# BMS_AFE_-_Cell_Inputs.net
KiCad netlist of a schematic drawn in Altium Designer
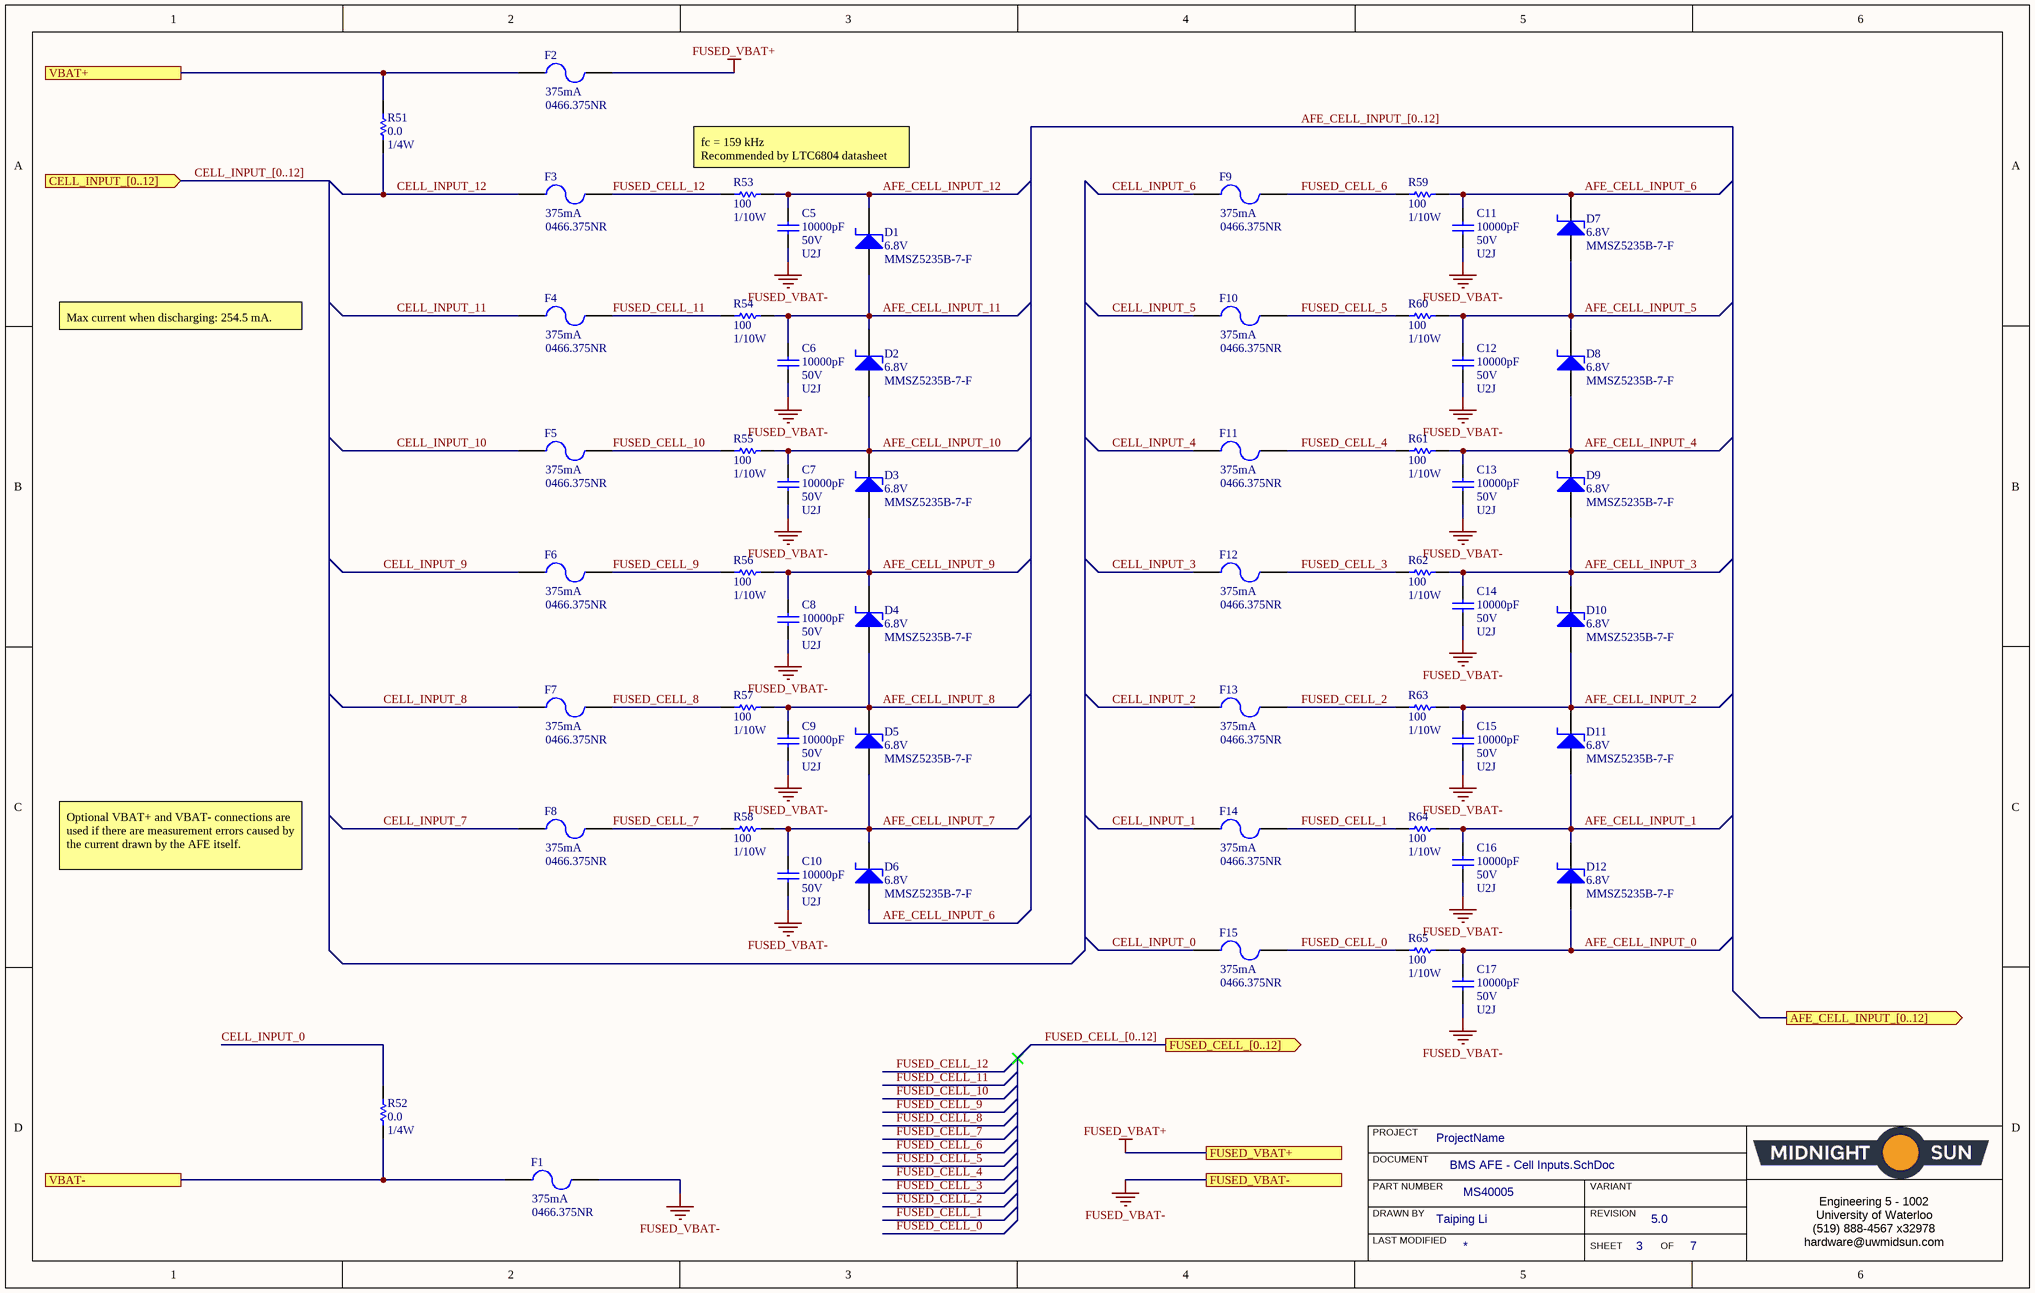
[diagram p0: BMS AFE - Cell Inputs.SchDoc]

(export (version "E")
  (design (tool "Eeschema 10.0.6"))
  (components
    (comp (ref "C5")
      (value "CAP CER 10nF 50V 5% X7R 0603")
      (footprint "CAP, 0603")
      (description "10000pF ±5% 50V Ceramic Capacitor U2J 0603 (1608 Metric)")
      (fields
        (field (name "TOLERANCE") "±5%")
        (field (name "CAPACITANCE") "10000pF")
        (field (name "VOLTAGE") "50V")
        (field (name "TEMPERATURE COEFFICIENT") "U2J")
      )
      (libsource (lib "Schematic Diagrams") (part "CAP CER 10nF 50V 5% X7R 0603"))
    )
    (comp (ref "C6")
      (value "CAP CER 10nF 50V 5% X7R 0603")
      (footprint "CAP, 0603")
      (description "10000pF ±5% 50V Ceramic Capacitor U2J 0603 (1608 Metric)")
      (fields
        (field (name "TOLERANCE") "±5%")
        (field (name "CAPACITANCE") "10000pF")
        (field (name "VOLTAGE") "50V")
        (field (name "TEMPERATURE COEFFICIENT") "U2J")
      )
      (libsource (lib "Schematic Diagrams") (part "CAP CER 10nF 50V 5% X7R 0603"))
    )
    (comp (ref "C7")
      (value "CAP CER 10nF 50V 5% X7R 0603")
      (footprint "CAP, 0603")
      (description "10000pF ±5% 50V Ceramic Capacitor U2J 0603 (1608 Metric)")
      (fields
        (field (name "TOLERANCE") "±5%")
        (field (name "CAPACITANCE") "10000pF")
        (field (name "VOLTAGE") "50V")
        (field (name "TEMPERATURE COEFFICIENT") "U2J")
      )
      (libsource (lib "Schematic Diagrams") (part "CAP CER 10nF 50V 5% X7R 0603"))
    )
    (comp (ref "C8")
      (value "CAP CER 10nF 50V 5% X7R 0603")
      (footprint "CAP, 0603")
      (description "10000pF ±5% 50V Ceramic Capacitor U2J 0603 (1608 Metric)")
      (fields
        (field (name "TOLERANCE") "±5%")
        (field (name "CAPACITANCE") "10000pF")
        (field (name "VOLTAGE") "50V")
        (field (name "TEMPERATURE COEFFICIENT") "U2J")
      )
      (libsource (lib "Schematic Diagrams") (part "CAP CER 10nF 50V 5% X7R 0603"))
    )
    (comp (ref "C9")
      (value "CAP CER 10nF 50V 5% X7R 0603")
      (footprint "CAP, 0603")
      (description "10000pF ±5% 50V Ceramic Capacitor U2J 0603 (1608 Metric)")
      (fields
        (field (name "TOLERANCE") "±5%")
        (field (name "CAPACITANCE") "10000pF")
        (field (name "VOLTAGE") "50V")
        (field (name "TEMPERATURE COEFFICIENT") "U2J")
      )
      (libsource (lib "Schematic Diagrams") (part "CAP CER 10nF 50V 5% X7R 0603"))
    )
    (comp (ref "C10")
      (value "CAP CER 10nF 50V 5% X7R 0603")
      (footprint "CAP, 0603")
      (description "10000pF ±5% 50V Ceramic Capacitor U2J 0603 (1608 Metric)")
      (fields
        (field (name "TOLERANCE") "±5%")
        (field (name "CAPACITANCE") "10000pF")
        (field (name "VOLTAGE") "50V")
        (field (name "TEMPERATURE COEFFICIENT") "U2J")
      )
      (libsource (lib "Schematic Diagrams") (part "CAP CER 10nF 50V 5% X7R 0603"))
    )
    (comp (ref "C11")
      (value "CAP CER 10nF 50V 5% X7R 0603")
      (footprint "CAP, 0603")
      (description "10000pF ±5% 50V Ceramic Capacitor U2J 0603 (1608 Metric)")
      (fields
        (field (name "TOLERANCE") "±5%")
        (field (name "CAPACITANCE") "10000pF")
        (field (name "VOLTAGE") "50V")
        (field (name "TEMPERATURE COEFFICIENT") "U2J")
      )
      (libsource (lib "Schematic Diagrams") (part "CAP CER 10nF 50V 5% X7R 0603"))
    )
    (comp (ref "C12")
      (value "CAP CER 10nF 50V 5% X7R 0603")
      (footprint "CAP, 0603")
      (description "10000pF ±5% 50V Ceramic Capacitor U2J 0603 (1608 Metric)")
      (fields
        (field (name "TOLERANCE") "±5%")
        (field (name "CAPACITANCE") "10000pF")
        (field (name "VOLTAGE") "50V")
        (field (name "TEMPERATURE COEFFICIENT") "U2J")
      )
      (libsource (lib "Schematic Diagrams") (part "CAP CER 10nF 50V 5% X7R 0603"))
    )
    (comp (ref "C13")
      (value "CAP CER 10nF 50V 5% X7R 0603")
      (footprint "CAP, 0603")
      (description "10000pF ±5% 50V Ceramic Capacitor U2J 0603 (1608 Metric)")
      (fields
        (field (name "TOLERANCE") "±5%")
        (field (name "CAPACITANCE") "10000pF")
        (field (name "VOLTAGE") "50V")
        (field (name "TEMPERATURE COEFFICIENT") "U2J")
      )
      (libsource (lib "Schematic Diagrams") (part "CAP CER 10nF 50V 5% X7R 0603"))
    )
    (comp (ref "C14")
      (value "CAP CER 10nF 50V 5% X7R 0603")
      (footprint "CAP, 0603")
      (description "10000pF ±5% 50V Ceramic Capacitor U2J 0603 (1608 Metric)")
      (fields
        (field (name "TOLERANCE") "±5%")
        (field (name "CAPACITANCE") "10000pF")
        (field (name "VOLTAGE") "50V")
        (field (name "TEMPERATURE COEFFICIENT") "U2J")
      )
      (libsource (lib "Schematic Diagrams") (part "CAP CER 10nF 50V 5% X7R 0603"))
    )
    (comp (ref "C15")
      (value "CAP CER 10nF 50V 5% X7R 0603")
      (footprint "CAP, 0603")
      (description "10000pF ±5% 50V Ceramic Capacitor U2J 0603 (1608 Metric)")
      (fields
        (field (name "TOLERANCE") "±5%")
        (field (name "CAPACITANCE") "10000pF")
        (field (name "VOLTAGE") "50V")
        (field (name "TEMPERATURE COEFFICIENT") "U2J")
      )
      (libsource (lib "Schematic Diagrams") (part "CAP CER 10nF 50V 5% X7R 0603"))
    )
    (comp (ref "C16")
      (value "CAP CER 10nF 50V 5% X7R 0603")
      (footprint "CAP, 0603")
      (description "10000pF ±5% 50V Ceramic Capacitor U2J 0603 (1608 Metric)")
      (fields
        (field (name "TOLERANCE") "±5%")
        (field (name "CAPACITANCE") "10000pF")
        (field (name "VOLTAGE") "50V")
        (field (name "TEMPERATURE COEFFICIENT") "U2J")
      )
      (libsource (lib "Schematic Diagrams") (part "CAP CER 10nF 50V 5% X7R 0603"))
    )
    (comp (ref "C17")
      (value "CAP CER 10nF 50V 5% X7R 0603")
      (footprint "CAP, 0603")
      (description "10000pF ±5% 50V Ceramic Capacitor U2J 0603 (1608 Metric)")
      (fields
        (field (name "TOLERANCE") "±5%")
        (field (name "CAPACITANCE") "10000pF")
        (field (name "VOLTAGE") "50V")
        (field (name "TEMPERATURE COEFFICIENT") "U2J")
      )
      (libsource (lib "Schematic Diagrams") (part "CAP CER 10nF 50V 5% X7R 0603"))
    )
    (comp (ref "D1")
      (value "6.8V")
      (footprint "DIODE SOD123")
      (description "Zener Diode 6.8V 500mW ±5% Surface Mount SOD-123")
      (fields
        (field (name "MANUFACTURER") "Diodes Incorporated")
        (field (name "TOLERANCE") "±5%")
        (field (name "MANUFACTURER PART NUMBER") "MMSZ5235B-7-F")
      )
      (libsource (lib "Schematic Diagrams") (part "DIODE ZENER 6.8V 500MW SOD123"))
    )
    (comp (ref "D2")
      (value "6.8V")
      (footprint "DIODE SOD123")
      (description "Zener Diode 6.8V 500mW ±5% Surface Mount SOD-123")
      (fields
        (field (name "MANUFACTURER") "Diodes Incorporated")
        (field (name "TOLERANCE") "±5%")
        (field (name "MANUFACTURER PART NUMBER") "MMSZ5235B-7-F")
      )
      (libsource (lib "Schematic Diagrams") (part "DIODE ZENER 6.8V 500MW SOD123"))
    )
    (comp (ref "D3")
      (value "6.8V")
      (footprint "DIODE SOD123")
      (description "Zener Diode 6.8V 500mW ±5% Surface Mount SOD-123")
      (fields
        (field (name "MANUFACTURER") "Diodes Incorporated")
        (field (name "TOLERANCE") "±5%")
        (field (name "MANUFACTURER PART NUMBER") "MMSZ5235B-7-F")
      )
      (libsource (lib "Schematic Diagrams") (part "DIODE ZENER 6.8V 500MW SOD123"))
    )
    (comp (ref "D4")
      (value "6.8V")
      (footprint "DIODE SOD123")
      (description "Zener Diode 6.8V 500mW ±5% Surface Mount SOD-123")
      (fields
        (field (name "MANUFACTURER") "Diodes Incorporated")
        (field (name "TOLERANCE") "±5%")
        (field (name "MANUFACTURER PART NUMBER") "MMSZ5235B-7-F")
      )
      (libsource (lib "Schematic Diagrams") (part "DIODE ZENER 6.8V 500MW SOD123"))
    )
    (comp (ref "D5")
      (value "6.8V")
      (footprint "DIODE SOD123")
      (description "Zener Diode 6.8V 500mW ±5% Surface Mount SOD-123")
      (fields
        (field (name "MANUFACTURER") "Diodes Incorporated")
        (field (name "TOLERANCE") "±5%")
        (field (name "MANUFACTURER PART NUMBER") "MMSZ5235B-7-F")
      )
      (libsource (lib "Schematic Diagrams") (part "DIODE ZENER 6.8V 500MW SOD123"))
    )
    (comp (ref "D6")
      (value "6.8V")
      (footprint "DIODE SOD123")
      (description "Zener Diode 6.8V 500mW ±5% Surface Mount SOD-123")
      (fields
        (field (name "MANUFACTURER") "Diodes Incorporated")
        (field (name "TOLERANCE") "±5%")
        (field (name "MANUFACTURER PART NUMBER") "MMSZ5235B-7-F")
      )
      (libsource (lib "Schematic Diagrams") (part "DIODE ZENER 6.8V 500MW SOD123"))
    )
    (comp (ref "D7")
      (value "6.8V")
      (footprint "DIODE SOD123")
      (description "Zener Diode 6.8V 500mW ±5% Surface Mount SOD-123")
      (fields
        (field (name "MANUFACTURER") "Diodes Incorporated")
        (field (name "TOLERANCE") "±5%")
        (field (name "MANUFACTURER PART NUMBER") "MMSZ5235B-7-F")
      )
      (libsource (lib "Schematic Diagrams") (part "DIODE ZENER 6.8V 500MW SOD123"))
    )
    (comp (ref "D8")
      (value "6.8V")
      (footprint "DIODE SOD123")
      (description "Zener Diode 6.8V 500mW ±5% Surface Mount SOD-123")
      (fields
        (field (name "MANUFACTURER") "Diodes Incorporated")
        (field (name "TOLERANCE") "±5%")
        (field (name "MANUFACTURER PART NUMBER") "MMSZ5235B-7-F")
      )
      (libsource (lib "Schematic Diagrams") (part "DIODE ZENER 6.8V 500MW SOD123"))
    )
    (comp (ref "D9")
      (value "6.8V")
      (footprint "DIODE SOD123")
      (description "Zener Diode 6.8V 500mW ±5% Surface Mount SOD-123")
      (fields
        (field (name "MANUFACTURER") "Diodes Incorporated")
        (field (name "TOLERANCE") "±5%")
        (field (name "MANUFACTURER PART NUMBER") "MMSZ5235B-7-F")
      )
      (libsource (lib "Schematic Diagrams") (part "DIODE ZENER 6.8V 500MW SOD123"))
    )
    (comp (ref "D10")
      (value "6.8V")
      (footprint "DIODE SOD123")
      (description "Zener Diode 6.8V 500mW ±5% Surface Mount SOD-123")
      (fields
        (field (name "MANUFACTURER") "Diodes Incorporated")
        (field (name "TOLERANCE") "±5%")
        (field (name "MANUFACTURER PART NUMBER") "MMSZ5235B-7-F")
      )
      (libsource (lib "Schematic Diagrams") (part "DIODE ZENER 6.8V 500MW SOD123"))
    )
    (comp (ref "D11")
      (value "6.8V")
      (footprint "DIODE SOD123")
      (description "Zener Diode 6.8V 500mW ±5% Surface Mount SOD-123")
      (fields
        (field (name "MANUFACTURER") "Diodes Incorporated")
        (field (name "TOLERANCE") "±5%")
        (field (name "MANUFACTURER PART NUMBER") "MMSZ5235B-7-F")
      )
      (libsource (lib "Schematic Diagrams") (part "DIODE ZENER 6.8V 500MW SOD123"))
    )
    (comp (ref "D12")
      (value "6.8V")
      (footprint "DIODE SOD123")
      (description "Zener Diode 6.8V 500mW ±5% Surface Mount SOD-123")
      (fields
        (field (name "MANUFACTURER") "Diodes Incorporated")
        (field (name "TOLERANCE") "±5%")
        (field (name "MANUFACTURER PART NUMBER") "MMSZ5235B-7-F")
      )
      (libsource (lib "Schematic Diagrams") (part "DIODE ZENER 6.8V 500MW SOD123"))
    )
    (comp (ref "F1")
      (value "375 mA")
      (footprint "FUSE LITTLEFUSE 0466 1206")
      (description "FUSE BOARD MNT 375MA 125VAC/VDC")
      (fields
        (field (name "MANUFACTURER") "Littelfuse")
        (field (name "MANUFACTURER PART NUMBER") "0466.375NR")
        (field (name "CURRENT RATING") "375mA")
      )
      (libsource (lib "Schematic Diagrams") (part "FUSE 375MA 125VDC 1206"))
    )
    (comp (ref "F2")
      (value "375 mA")
      (footprint "FUSE LITTLEFUSE 0466 1206")
      (description "FUSE BOARD MNT 375MA 125VAC/VDC")
      (fields
        (field (name "MANUFACTURER") "Littelfuse")
        (field (name "MANUFACTURER PART NUMBER") "0466.375NR")
        (field (name "CURRENT RATING") "375mA")
      )
      (libsource (lib "Schematic Diagrams") (part "FUSE 375MA 125VDC 1206"))
    )
    (comp (ref "F3")
      (value "375 mA")
      (footprint "FUSE LITTLEFUSE 0466 1206")
      (description "FUSE BOARD MNT 375MA 125VAC/VDC")
      (fields
        (field (name "MANUFACTURER") "Littelfuse")
        (field (name "MANUFACTURER PART NUMBER") "0466.375NR")
        (field (name "CURRENT RATING") "375mA")
      )
      (libsource (lib "Schematic Diagrams") (part "FUSE 375MA 125VDC 1206"))
    )
    (comp (ref "F4")
      (value "375 mA")
      (footprint "FUSE LITTLEFUSE 0466 1206")
      (description "FUSE BOARD MNT 375MA 125VAC/VDC")
      (fields
        (field (name "MANUFACTURER") "Littelfuse")
        (field (name "MANUFACTURER PART NUMBER") "0466.375NR")
        (field (name "CURRENT RATING") "375mA")
      )
      (libsource (lib "Schematic Diagrams") (part "FUSE 375MA 125VDC 1206"))
    )
    (comp (ref "F5")
      (value "375 mA")
      (footprint "FUSE LITTLEFUSE 0466 1206")
      (description "FUSE BOARD MNT 375MA 125VAC/VDC")
      (fields
        (field (name "MANUFACTURER") "Littelfuse")
        (field (name "MANUFACTURER PART NUMBER") "0466.375NR")
        (field (name "CURRENT RATING") "375mA")
      )
      (libsource (lib "Schematic Diagrams") (part "FUSE 375MA 125VDC 1206"))
    )
    (comp (ref "F6")
      (value "375 mA")
      (footprint "FUSE LITTLEFUSE 0466 1206")
      (description "FUSE BOARD MNT 375MA 125VAC/VDC")
      (fields
        (field (name "MANUFACTURER") "Littelfuse")
        (field (name "MANUFACTURER PART NUMBER") "0466.375NR")
        (field (name "CURRENT RATING") "375mA")
      )
      (libsource (lib "Schematic Diagrams") (part "FUSE 375MA 125VDC 1206"))
    )
    (comp (ref "F7")
      (value "375 mA")
      (footprint "FUSE LITTLEFUSE 0466 1206")
      (description "FUSE BOARD MNT 375MA 125VAC/VDC")
      (fields
        (field (name "MANUFACTURER") "Littelfuse")
        (field (name "MANUFACTURER PART NUMBER") "0466.375NR")
        (field (name "CURRENT RATING") "375mA")
      )
      (libsource (lib "Schematic Diagrams") (part "FUSE 375MA 125VDC 1206"))
    )
    (comp (ref "F8")
      (value "375 mA")
      (footprint "FUSE LITTLEFUSE 0466 1206")
      (description "FUSE BOARD MNT 375MA 125VAC/VDC")
      (fields
        (field (name "MANUFACTURER") "Littelfuse")
        (field (name "MANUFACTURER PART NUMBER") "0466.375NR")
        (field (name "CURRENT RATING") "375mA")
      )
      (libsource (lib "Schematic Diagrams") (part "FUSE 375MA 125VDC 1206"))
    )
    (comp (ref "F9")
      (value "375 mA")
      (footprint "FUSE LITTLEFUSE 0466 1206")
      (description "FUSE BOARD MNT 375MA 125VAC/VDC")
      (fields
        (field (name "MANUFACTURER") "Littelfuse")
        (field (name "MANUFACTURER PART NUMBER") "0466.375NR")
        (field (name "CURRENT RATING") "375mA")
      )
      (libsource (lib "Schematic Diagrams") (part "FUSE 375MA 125VDC 1206"))
    )
    (comp (ref "F10")
      (value "375 mA")
      (footprint "FUSE LITTLEFUSE 0466 1206")
      (description "FUSE BOARD MNT 375MA 125VAC/VDC")
      (fields
        (field (name "MANUFACTURER") "Littelfuse")
        (field (name "MANUFACTURER PART NUMBER") "0466.375NR")
        (field (name "CURRENT RATING") "375mA")
      )
      (libsource (lib "Schematic Diagrams") (part "FUSE 375MA 125VDC 1206"))
    )
    (comp (ref "F11")
      (value "375 mA")
      (footprint "FUSE LITTLEFUSE 0466 1206")
      (description "FUSE BOARD MNT 375MA 125VAC/VDC")
      (fields
        (field (name "MANUFACTURER") "Littelfuse")
        (field (name "MANUFACTURER PART NUMBER") "0466.375NR")
        (field (name "CURRENT RATING") "375mA")
      )
      (libsource (lib "Schematic Diagrams") (part "FUSE 375MA 125VDC 1206"))
    )
    (comp (ref "F12")
      (value "375 mA")
      (footprint "FUSE LITTLEFUSE 0466 1206")
      (description "FUSE BOARD MNT 375MA 125VAC/VDC")
      (fields
        (field (name "MANUFACTURER") "Littelfuse")
        (field (name "MANUFACTURER PART NUMBER") "0466.375NR")
        (field (name "CURRENT RATING") "375mA")
      )
      (libsource (lib "Schematic Diagrams") (part "FUSE 375MA 125VDC 1206"))
    )
    (comp (ref "F13")
      (value "375 mA")
      (footprint "FUSE LITTLEFUSE 0466 1206")
      (description "FUSE BOARD MNT 375MA 125VAC/VDC")
      (fields
        (field (name "MANUFACTURER") "Littelfuse")
        (field (name "MANUFACTURER PART NUMBER") "0466.375NR")
        (field (name "CURRENT RATING") "375mA")
      )
      (libsource (lib "Schematic Diagrams") (part "FUSE 375MA 125VDC 1206"))
    )
    (comp (ref "F14")
      (value "375 mA")
      (footprint "FUSE LITTLEFUSE 0466 1206")
      (description "FUSE BOARD MNT 375MA 125VAC/VDC")
      (fields
        (field (name "MANUFACTURER") "Littelfuse")
        (field (name "MANUFACTURER PART NUMBER") "0466.375NR")
        (field (name "CURRENT RATING") "375mA")
      )
      (libsource (lib "Schematic Diagrams") (part "FUSE 375MA 125VDC 1206"))
    )
    (comp (ref "F15")
      (value "375 mA")
      (footprint "FUSE LITTLEFUSE 0466 1206")
      (description "FUSE BOARD MNT 375MA 125VAC/VDC")
      (fields
        (field (name "MANUFACTURER") "Littelfuse")
        (field (name "MANUFACTURER PART NUMBER") "0466.375NR")
        (field (name "CURRENT RATING") "375mA")
      )
      (libsource (lib "Schematic Diagrams") (part "FUSE 375MA 125VDC 1206"))
    )
    (comp (ref "R51")
      (value "RES 0.0 OHM 1/4W 0603")
      (footprint "RES, 0603")
      (description "RES SMD 0.0 OHM JUMPER 1/4W 0603")
      (fields (field (name "RESISTANCE") "0.0") (field (name "POWER (WATTS)") "1/4W"))
      (libsource (lib "Schematic Diagrams") (part "RES 0.0 OHM 1/4W 0603"))
    )
    (comp (ref "R52")
      (value "RES 0.0 OHM 1/4W 0603")
      (footprint "RES, 0603")
      (description "RES SMD 0.0 OHM JUMPER 1/4W 0603")
      (fields (field (name "RESISTANCE") "0.0") (field (name "POWER (WATTS)") "1/4W"))
      (libsource (lib "Schematic Diagrams") (part "RES 0.0 OHM 1/4W 0603"))
    )
    (comp (ref "R53")
      (value "RES 100 OHM 1% 1/10W 0603")
      (footprint "RES, 0603")
      (description "100 Ohm ±1% 0.1W, 1/10W Chip Resistor 0603 (1608 Metric) Moisture Resistant Thick Film")
      (fields
        (field (name "TOLERANCE") "±1%")
        (field (name "RESISTANCE") "100")
        (field (name "POWER") "1/10W")
      )
      (libsource (lib "Schematic Diagrams") (part "RES 100 OHM 1% 1/10W 0603"))
    )
    (comp (ref "R54")
      (value "RES 100 OHM 1% 1/10W 0603")
      (footprint "RES, 0603")
      (description "100 Ohm ±1% 0.1W, 1/10W Chip Resistor 0603 (1608 Metric) Moisture Resistant Thick Film")
      (fields
        (field (name "TOLERANCE") "±1%")
        (field (name "RESISTANCE") "100")
        (field (name "POWER") "1/10W")
      )
      (libsource (lib "Schematic Diagrams") (part "RES 100 OHM 1% 1/10W 0603"))
    )
    (comp (ref "R55")
      (value "RES 100 OHM 1% 1/10W 0603")
      (footprint "RES, 0603")
      (description "100 Ohm ±1% 0.1W, 1/10W Chip Resistor 0603 (1608 Metric) Moisture Resistant Thick Film")
      (fields
        (field (name "TOLERANCE") "±1%")
        (field (name "RESISTANCE") "100")
        (field (name "POWER") "1/10W")
      )
      (libsource (lib "Schematic Diagrams") (part "RES 100 OHM 1% 1/10W 0603"))
    )
    (comp (ref "R56")
      (value "RES 100 OHM 1% 1/10W 0603")
      (footprint "RES, 0603")
      (description "100 Ohm ±1% 0.1W, 1/10W Chip Resistor 0603 (1608 Metric) Moisture Resistant Thick Film")
      (fields
        (field (name "TOLERANCE") "±1%")
        (field (name "RESISTANCE") "100")
        (field (name "POWER") "1/10W")
      )
      (libsource (lib "Schematic Diagrams") (part "RES 100 OHM 1% 1/10W 0603"))
    )
    (comp (ref "R57")
      (value "RES 100 OHM 1% 1/10W 0603")
      (footprint "RES, 0603")
      (description "100 Ohm ±1% 0.1W, 1/10W Chip Resistor 0603 (1608 Metric) Moisture Resistant Thick Film")
      (fields
        (field (name "TOLERANCE") "±1%")
        (field (name "RESISTANCE") "100")
        (field (name "POWER") "1/10W")
      )
      (libsource (lib "Schematic Diagrams") (part "RES 100 OHM 1% 1/10W 0603"))
    )
    (comp (ref "R58")
      (value "RES 100 OHM 1% 1/10W 0603")
      (footprint "RES, 0603")
      (description "100 Ohm ±1% 0.1W, 1/10W Chip Resistor 0603 (1608 Metric) Moisture Resistant Thick Film")
      (fields
        (field (name "TOLERANCE") "±1%")
        (field (name "RESISTANCE") "100")
        (field (name "POWER") "1/10W")
      )
      (libsource (lib "Schematic Diagrams") (part "RES 100 OHM 1% 1/10W 0603"))
    )
    (comp (ref "R59")
      (value "RES 100 OHM 1% 1/10W 0603")
      (footprint "RES, 0603")
      (description "100 Ohm ±1% 0.1W, 1/10W Chip Resistor 0603 (1608 Metric) Moisture Resistant Thick Film")
      (fields
        (field (name "TOLERANCE") "±1%")
        (field (name "RESISTANCE") "100")
        (field (name "POWER") "1/10W")
      )
      (libsource (lib "Schematic Diagrams") (part "RES 100 OHM 1% 1/10W 0603"))
    )
    (comp (ref "R60")
      (value "RES 100 OHM 1% 1/10W 0603")
      (footprint "RES, 0603")
      (description "100 Ohm ±1% 0.1W, 1/10W Chip Resistor 0603 (1608 Metric) Moisture Resistant Thick Film")
      (fields
        (field (name "TOLERANCE") "±1%")
        (field (name "RESISTANCE") "100")
        (field (name "POWER") "1/10W")
      )
      (libsource (lib "Schematic Diagrams") (part "RES 100 OHM 1% 1/10W 0603"))
    )
    (comp (ref "R61")
      (value "RES 100 OHM 1% 1/10W 0603")
      (footprint "RES, 0603")
      (description "100 Ohm ±1% 0.1W, 1/10W Chip Resistor 0603 (1608 Metric) Moisture Resistant Thick Film")
      (fields
        (field (name "TOLERANCE") "±1%")
        (field (name "RESISTANCE") "100")
        (field (name "POWER") "1/10W")
      )
      (libsource (lib "Schematic Diagrams") (part "RES 100 OHM 1% 1/10W 0603"))
    )
    (comp (ref "R62")
      (value "RES 100 OHM 1% 1/10W 0603")
      (footprint "RES, 0603")
      (description "100 Ohm ±1% 0.1W, 1/10W Chip Resistor 0603 (1608 Metric) Moisture Resistant Thick Film")
      (fields
        (field (name "TOLERANCE") "±1%")
        (field (name "RESISTANCE") "100")
        (field (name "POWER") "1/10W")
      )
      (libsource (lib "Schematic Diagrams") (part "RES 100 OHM 1% 1/10W 0603"))
    )
    (comp (ref "R63")
      (value "RES 100 OHM 1% 1/10W 0603")
      (footprint "RES, 0603")
      (description "100 Ohm ±1% 0.1W, 1/10W Chip Resistor 0603 (1608 Metric) Moisture Resistant Thick Film")
      (fields
        (field (name "TOLERANCE") "±1%")
        (field (name "RESISTANCE") "100")
        (field (name "POWER") "1/10W")
      )
      (libsource (lib "Schematic Diagrams") (part "RES 100 OHM 1% 1/10W 0603"))
    )
    (comp (ref "R64")
      (value "RES 100 OHM 1% 1/10W 0603")
      (footprint "RES, 0603")
      (description "100 Ohm ±1% 0.1W, 1/10W Chip Resistor 0603 (1608 Metric) Moisture Resistant Thick Film")
      (fields
        (field (name "TOLERANCE") "±1%")
        (field (name "RESISTANCE") "100")
        (field (name "POWER") "1/10W")
      )
      (libsource (lib "Schematic Diagrams") (part "RES 100 OHM 1% 1/10W 0603"))
    )
    (comp (ref "R65")
      (value "RES 100 OHM 1% 1/10W 0603")
      (footprint "RES, 0603")
      (description "100 Ohm ±1% 0.1W, 1/10W Chip Resistor 0603 (1608 Metric) Moisture Resistant Thick Film")
      (fields
        (field (name "TOLERANCE") "±1%")
        (field (name "RESISTANCE") "100")
        (field (name "POWER") "1/10W")
      )
      (libsource (lib "Schematic Diagrams") (part "RES 100 OHM 1% 1/10W 0603"))
    )
  )
  (nets
    (net (code "1") (name "/AFE_CELL_INPUT_0") (class "Default")
      (node (ref "C17") (pin "1") (pinfunction "1_1") (pintype "passive"))
      (node (ref "D12") (pin "2") (pinfunction "A_2") (pintype "passive"))
      (node (ref "R65") (pin "2") (pinfunction "2_2") (pintype "passive"))
    )
    (net (code "2") (name "/AFE_CELL_INPUT_1") (class "Default")
      (node (ref "C16") (pin "1") (pinfunction "1_1") (pintype "passive"))
      (node (ref "D11") (pin "2") (pinfunction "A_2") (pintype "passive"))
      (node (ref "D12") (pin "1") (pinfunction "K_1") (pintype "passive"))
      (node (ref "R64") (pin "2") (pinfunction "2_2") (pintype "passive"))
    )
    (net (code "3") (name "/AFE_CELL_INPUT_2") (class "Default")
      (node (ref "C15") (pin "1") (pinfunction "1_1") (pintype "passive"))
      (node (ref "D10") (pin "2") (pinfunction "A_2") (pintype "passive"))
      (node (ref "D11") (pin "1") (pinfunction "K_1") (pintype "passive"))
      (node (ref "R63") (pin "2") (pinfunction "2_2") (pintype "passive"))
    )
    (net (code "4") (name "/AFE_CELL_INPUT_3") (class "Default")
      (node (ref "C14") (pin "1") (pinfunction "1_1") (pintype "passive"))
      (node (ref "D10") (pin "1") (pinfunction "K_1") (pintype "passive"))
      (node (ref "D9") (pin "2") (pinfunction "A_2") (pintype "passive"))
      (node (ref "R62") (pin "2") (pinfunction "2_2") (pintype "passive"))
    )
    (net (code "5") (name "/AFE_CELL_INPUT_4") (class "Default")
      (node (ref "C13") (pin "1") (pinfunction "1_1") (pintype "passive"))
      (node (ref "D8") (pin "2") (pinfunction "A_2") (pintype "passive"))
      (node (ref "D9") (pin "1") (pinfunction "K_1") (pintype "passive"))
      (node (ref "R61") (pin "2") (pinfunction "2_2") (pintype "passive"))
    )
    (net (code "6") (name "/AFE_CELL_INPUT_5") (class "Default")
      (node (ref "C12") (pin "1") (pinfunction "1_1") (pintype "passive"))
      (node (ref "D7") (pin "2") (pinfunction "A_2") (pintype "passive"))
      (node (ref "D8") (pin "1") (pinfunction "K_1") (pintype "passive"))
      (node (ref "R60") (pin "2") (pinfunction "2_2") (pintype "passive"))
    )
    (net (code "7") (name "/AFE_CELL_INPUT_6") (class "Default")
      (node (ref "C11") (pin "1") (pinfunction "1_1") (pintype "passive"))
      (node (ref "D6") (pin "2") (pinfunction "A_2") (pintype "passive"))
      (node (ref "D7") (pin "1") (pinfunction "K_1") (pintype "passive"))
      (node (ref "R59") (pin "2") (pinfunction "2_2") (pintype "passive"))
    )
    (net (code "8") (name "/AFE_CELL_INPUT_7") (class "Default")
      (node (ref "C10") (pin "1") (pinfunction "1_1") (pintype "passive"))
      (node (ref "D5") (pin "2") (pinfunction "A_2") (pintype "passive"))
      (node (ref "D6") (pin "1") (pinfunction "K_1") (pintype "passive"))
      (node (ref "R58") (pin "2") (pinfunction "2_2") (pintype "passive"))
    )
    (net (code "9") (name "/AFE_CELL_INPUT_8") (class "Default")
      (node (ref "C9") (pin "1") (pinfunction "1_1") (pintype "passive"))
      (node (ref "D4") (pin "2") (pinfunction "A_2") (pintype "passive"))
      (node (ref "D5") (pin "1") (pinfunction "K_1") (pintype "passive"))
      (node (ref "R57") (pin "2") (pinfunction "2_2") (pintype "passive"))
    )
    (net (code "10") (name "/AFE_CELL_INPUT_9") (class "Default")
      (node (ref "C8") (pin "1") (pinfunction "1_1") (pintype "passive"))
      (node (ref "D3") (pin "2") (pinfunction "A_2") (pintype "passive"))
      (node (ref "D4") (pin "1") (pinfunction "K_1") (pintype "passive"))
      (node (ref "R56") (pin "2") (pinfunction "2_2") (pintype "passive"))
    )
    (net (code "11") (name "/AFE_CELL_INPUT_10") (class "Default")
      (node (ref "C7") (pin "1") (pinfunction "1_1") (pintype "passive"))
      (node (ref "D2") (pin "2") (pinfunction "A_2") (pintype "passive"))
      (node (ref "D3") (pin "1") (pinfunction "K_1") (pintype "passive"))
      (node (ref "R55") (pin "2") (pinfunction "2_2") (pintype "passive"))
    )
    (net (code "12") (name "/AFE_CELL_INPUT_11") (class "Default")
      (node (ref "C6") (pin "1") (pinfunction "1_1") (pintype "passive"))
      (node (ref "D1") (pin "2") (pinfunction "A_2") (pintype "passive"))
      (node (ref "D2") (pin "1") (pinfunction "K_1") (pintype "passive"))
      (node (ref "R54") (pin "2") (pinfunction "2_2") (pintype "passive"))
    )
    (net (code "13") (name "/AFE_CELL_INPUT_12") (class "Default")
      (node (ref "C5") (pin "1") (pinfunction "1_1") (pintype "passive"))
      (node (ref "D1") (pin "1") (pinfunction "K_1") (pintype "passive"))
      (node (ref "R53") (pin "2") (pinfunction "2_2") (pintype "passive"))
    )
    (net (code "15") (name "/CELL_INPUT_0") (class "Default")
      (node (ref "F15") (pin "1") (pinfunction "1_1") (pintype "passive"))
      (node (ref "R52") (pin "1") (pinfunction "1_1") (pintype "passive"))
    )
    (net (code "16") (name "/CELL_INPUT_1") (class "Default")
      (node (ref "F14") (pin "1") (pinfunction "1_1") (pintype "passive"))
    )
    (net (code "17") (name "/CELL_INPUT_2") (class "Default")
      (node (ref "F13") (pin "1") (pinfunction "1_1") (pintype "passive"))
    )
    (net (code "18") (name "/CELL_INPUT_3") (class "Default")
      (node (ref "F12") (pin "1") (pinfunction "1_1") (pintype "passive"))
    )
    (net (code "19") (name "/CELL_INPUT_4") (class "Default")
      (node (ref "F11") (pin "1") (pinfunction "1_1") (pintype "passive"))
    )
    (net (code "20") (name "/CELL_INPUT_5") (class "Default")
      (node (ref "F10") (pin "1") (pinfunction "1_1") (pintype "passive"))
    )
    (net (code "21") (name "/CELL_INPUT_6") (class "Default")
      (node (ref "F9") (pin "1") (pinfunction "1_1") (pintype "passive"))
    )
    (net (code "22") (name "/CELL_INPUT_7") (class "Default")
      (node (ref "F8") (pin "1") (pinfunction "1_1") (pintype "passive"))
    )
    (net (code "23") (name "/CELL_INPUT_8") (class "Default")
      (node (ref "F7") (pin "1") (pinfunction "1_1") (pintype "passive"))
    )
    (net (code "24") (name "/CELL_INPUT_9") (class "Default")
      (node (ref "F6") (pin "1") (pinfunction "1_1") (pintype "passive"))
    )
    (net (code "25") (name "/CELL_INPUT_10") (class "Default")
      (node (ref "F5") (pin "1") (pinfunction "1_1") (pintype "passive"))
    )
    (net (code "26") (name "/CELL_INPUT_11") (class "Default")
      (node (ref "F4") (pin "1") (pinfunction "1_1") (pintype "passive"))
    )
    (net (code "27") (name "/CELL_INPUT_12") (class "Default")
      (node (ref "F3") (pin "1") (pinfunction "1_1") (pintype "passive"))
      (node (ref "R51") (pin "2") (pinfunction "2_2") (pintype "passive"))
    )
    (net (code "29") (name "/FUSED_CELL_0") (class "Default")
      (node (ref "F15") (pin "2") (pinfunction "2_2") (pintype "passive"))
      (node (ref "R65") (pin "1") (pinfunction "1_1") (pintype "passive"))
    )
    (net (code "30") (name "/FUSED_CELL_1") (class "Default")
      (node (ref "F14") (pin "2") (pinfunction "2_2") (pintype "passive"))
      (node (ref "R64") (pin "1") (pinfunction "1_1") (pintype "passive"))
    )
    (net (code "31") (name "/FUSED_CELL_2") (class "Default")
      (node (ref "F13") (pin "2") (pinfunction "2_2") (pintype "passive"))
      (node (ref "R63") (pin "1") (pinfunction "1_1") (pintype "passive"))
    )
    (net (code "32") (name "/FUSED_CELL_3") (class "Default")
      (node (ref "F12") (pin "2") (pinfunction "2_2") (pintype "passive"))
      (node (ref "R62") (pin "1") (pinfunction "1_1") (pintype "passive"))
    )
    (net (code "33") (name "/FUSED_CELL_4") (class "Default")
      (node (ref "F11") (pin "2") (pinfunction "2_2") (pintype "passive"))
      (node (ref "R61") (pin "1") (pinfunction "1_1") (pintype "passive"))
    )
    (net (code "34") (name "/FUSED_CELL_5") (class "Default")
      (node (ref "F10") (pin "2") (pinfunction "2_2") (pintype "passive"))
      (node (ref "R60") (pin "1") (pinfunction "1_1") (pintype "passive"))
    )
    (net (code "35") (name "/FUSED_CELL_6") (class "Default")
      (node (ref "F9") (pin "2") (pinfunction "2_2") (pintype "passive"))
      (node (ref "R59") (pin "1") (pinfunction "1_1") (pintype "passive"))
    )
    (net (code "36") (name "/FUSED_CELL_7") (class "Default")
      (node (ref "F8") (pin "2") (pinfunction "2_2") (pintype "passive"))
      (node (ref "R58") (pin "1") (pinfunction "1_1") (pintype "passive"))
    )
    (net (code "37") (name "/FUSED_CELL_8") (class "Default")
      (node (ref "F7") (pin "2") (pinfunction "2_2") (pintype "passive"))
      (node (ref "R57") (pin "1") (pinfunction "1_1") (pintype "passive"))
    )
    (net (code "38") (name "/FUSED_CELL_9") (class "Default")
      (node (ref "F6") (pin "2") (pinfunction "2_2") (pintype "passive"))
      (node (ref "R56") (pin "1") (pinfunction "1_1") (pintype "passive"))
    )
    (net (code "39") (name "/FUSED_CELL_10") (class "Default")
      (node (ref "F5") (pin "2") (pinfunction "2_2") (pintype "passive"))
      (node (ref "R55") (pin "1") (pinfunction "1_1") (pintype "passive"))
    )
    (net (code "40") (name "/FUSED_CELL_11") (class "Default")
      (node (ref "F4") (pin "2") (pinfunction "2_2") (pintype "passive"))
      (node (ref "R54") (pin "1") (pinfunction "1_1") (pintype "passive"))
    )
    (net (code "41") (name "/FUSED_CELL_12") (class "Default")
      (node (ref "F3") (pin "2") (pinfunction "2_2") (pintype "passive"))
      (node (ref "R53") (pin "1") (pinfunction "1_1") (pintype "passive"))
    )
    (net (code "43") (name "/VBAT+") (class "Default")
      (node (ref "F2") (pin "1") (pinfunction "1_1") (pintype "passive"))
      (node (ref "R51") (pin "1") (pinfunction "1_1") (pintype "passive"))
    )
    (net (code "44") (name "/VBAT-") (class "Default")
      (node (ref "F1") (pin "1") (pinfunction "1_1") (pintype "passive"))
      (node (ref "R52") (pin "2") (pinfunction "2_2") (pintype "passive"))
    )
    (net (code "45") (name "FUSED_VBAT+") (class "Default")
      (node (ref "F2") (pin "2") (pinfunction "2_2") (pintype "passive"))
    )
    (net (code "46") (name "FUSED_VBAT-") (class "Default")
      (node (ref "C10") (pin "2") (pinfunction "2_2") (pintype "passive"))
      (node (ref "C11") (pin "2") (pinfunction "2_2") (pintype "passive"))
      (node (ref "C12") (pin "2") (pinfunction "2_2") (pintype "passive"))
      (node (ref "C13") (pin "2") (pinfunction "2_2") (pintype "passive"))
      (node (ref "C14") (pin "2") (pinfunction "2_2") (pintype "passive"))
      (node (ref "C15") (pin "2") (pinfunction "2_2") (pintype "passive"))
      (node (ref "C16") (pin "2") (pinfunction "2_2") (pintype "passive"))
      (node (ref "C17") (pin "2") (pinfunction "2_2") (pintype "passive"))
      (node (ref "C5") (pin "2") (pinfunction "2_2") (pintype "passive"))
      (node (ref "C6") (pin "2") (pinfunction "2_2") (pintype "passive"))
      (node (ref "C7") (pin "2") (pinfunction "2_2") (pintype "passive"))
      (node (ref "C8") (pin "2") (pinfunction "2_2") (pintype "passive"))
      (node (ref "C9") (pin "2") (pinfunction "2_2") (pintype "passive"))
      (node (ref "F1") (pin "2") (pinfunction "2_2") (pintype "passive"))
    )
  )
)
